# LoRa.net
KiCad netlist of a schematic drawn in Altium Designer
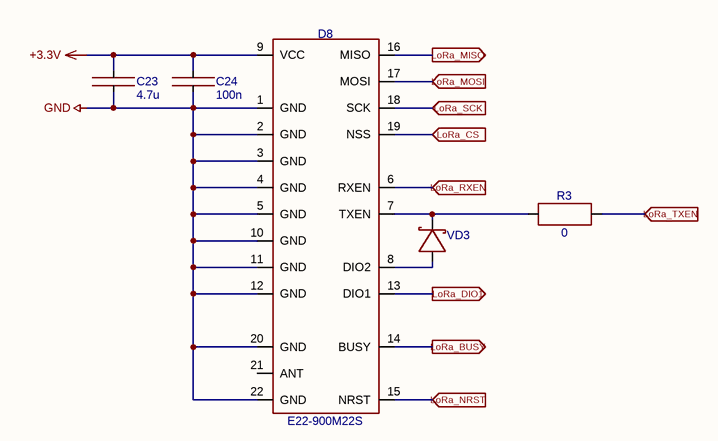
[diagram p0: LoRa.SchDoc]

(export (version "E")
  (design (tool "Eeschema 10.0.6"))
  (components
    (comp (ref "C23")
      (value "4.7u")
      (footprint "CAPC1608X09N")
      (description "GRM188R61A475K")
      (libsource (lib "Capasitors") (part "C0603-4.7u-10V-X5R-10%"))
    )
    (comp (ref "C24")
      (value "100n")
      (footprint "CAPC1608X09N")
      (description "GRM188R71E104KA01D")
      (libsource (lib "Capasitors") (part "C0603-100n-25V-X7R-10%"))
    )
    (comp (ref "D8")
      (value "E22-900M22S")
      (footprint "EBYTE E22")
      (libsource (lib "Wireless Modules") (part "E22-900M22S"))
    )
    (comp (ref "R3") (value "0") (footprint "RESC1608X05N") (libsource (lib "Resistors") (part "R-0603-0")))
    (comp (ref "VD3")
      (value "BAR6402VH6327XTSA1")
      (footprint "INFENION SC79")
      (libsource (lib "Diodes") (part "BAR6402VH6327XTSA1"))
    )
  )
  (nets
    (net (code "1") (name "+3.3V") (class "Default")
      (node (ref "C23") (pin "2") (pinfunction "2_2") (pintype "passive"))
      (node (ref "C24") (pin "2") (pinfunction "2_2") (pintype "passive"))
      (node (ref "D8") (pin "9") (pinfunction "VCC_9") (pintype "passive"))
    )
    (net (code "2") (name "/LoRa_BUSY") (class "Default")
      (node (ref "D8") (pin "14") (pinfunction "BUSY_14") (pintype "passive"))
    )
    (net (code "3") (name "/LoRa_CS") (class "Default")
      (node (ref "D8") (pin "19") (pinfunction "NSS_19") (pintype "passive"))
    )
    (net (code "4") (name "/LoRa_DIO1") (class "Default")
      (node (ref "D8") (pin "13") (pinfunction "DIO1_13") (pintype "passive"))
    )
    (net (code "5") (name "/LoRa_MISO") (class "Default")
      (node (ref "D8") (pin "16") (pinfunction "MISO_16") (pintype "passive"))
    )
    (net (code "6") (name "/LoRa_MOSI") (class "Default")
      (node (ref "D8") (pin "17") (pinfunction "MOSI_17") (pintype "passive"))
    )
    (net (code "7") (name "/LoRa_NRST") (class "Default")
      (node (ref "D8") (pin "15") (pinfunction "NRST_15") (pintype "passive"))
    )
    (net (code "8") (name "/LoRa_RXEN") (class "Default")
      (node (ref "D8") (pin "6") (pinfunction "RXEN_6") (pintype "passive"))
    )
    (net (code "9") (name "/LoRa_SCK") (class "Default")
      (node (ref "D8") (pin "18") (pinfunction "SCK_18") (pintype "passive"))
    )
    (net (code "10") (name "/LoRa_TXEN") (class "Default")
      (node (ref "R3") (pin "2") (pinfunction "2_2") (pintype "passive"))
    )
    (net (code "11") (name "GND") (class "Default")
      (node (ref "C23") (pin "1") (pinfunction "1_1") (pintype "passive"))
      (node (ref "C24") (pin "1") (pinfunction "1_1") (pintype "passive"))
      (node (ref "D8") (pin "1") (pinfunction "GND_1") (pintype "passive"))
      (node (ref "D8") (pin "10") (pinfunction "GND_10") (pintype "passive"))
      (node (ref "D8") (pin "11") (pinfunction "GND_11") (pintype "passive"))
      (node (ref "D8") (pin "12") (pinfunction "GND_12") (pintype "passive"))
      (node (ref "D8") (pin "2") (pinfunction "GND_2") (pintype "passive"))
      (node (ref "D8") (pin "20") (pinfunction "GND_20") (pintype "passive"))
      (node (ref "D8") (pin "22") (pinfunction "GND_22") (pintype "passive"))
      (node (ref "D8") (pin "3") (pinfunction "GND_3") (pintype "passive"))
      (node (ref "D8") (pin "4") (pinfunction "GND_4") (pintype "passive"))
      (node (ref "D8") (pin "5") (pinfunction "GND_5") (pintype "passive"))
    )
    (net (code "12") (name "Net-(D8-DIO2)") (class "Default")
      (node (ref "D8") (pin "8") (pinfunction "DIO2_8") (pintype "passive"))
      (node (ref "VD3") (pin "2") (pinfunction "2_2") (pintype "passive"))
    )
    (net (code "13") (name "Net-(D8-TXEN)") (class "Default")
      (node (ref "D8") (pin "7") (pinfunction "TXEN_7") (pintype "passive"))
      (node (ref "R3") (pin "1") (pinfunction "1_1") (pintype "passive"))
      (node (ref "VD3") (pin "1") (pinfunction "1_1") (pintype "passive"))
    )
    (net (code "14") (name "unconnected-(D8-ANT-Pad21)") (class "Default")
      (node (ref "D8") (pin "21") (pinfunction "ANT_21") (pintype "passive"))
    )
  )
)
